# As_Shipped.net
KiCad netlist of a schematic drawn in EAGLE
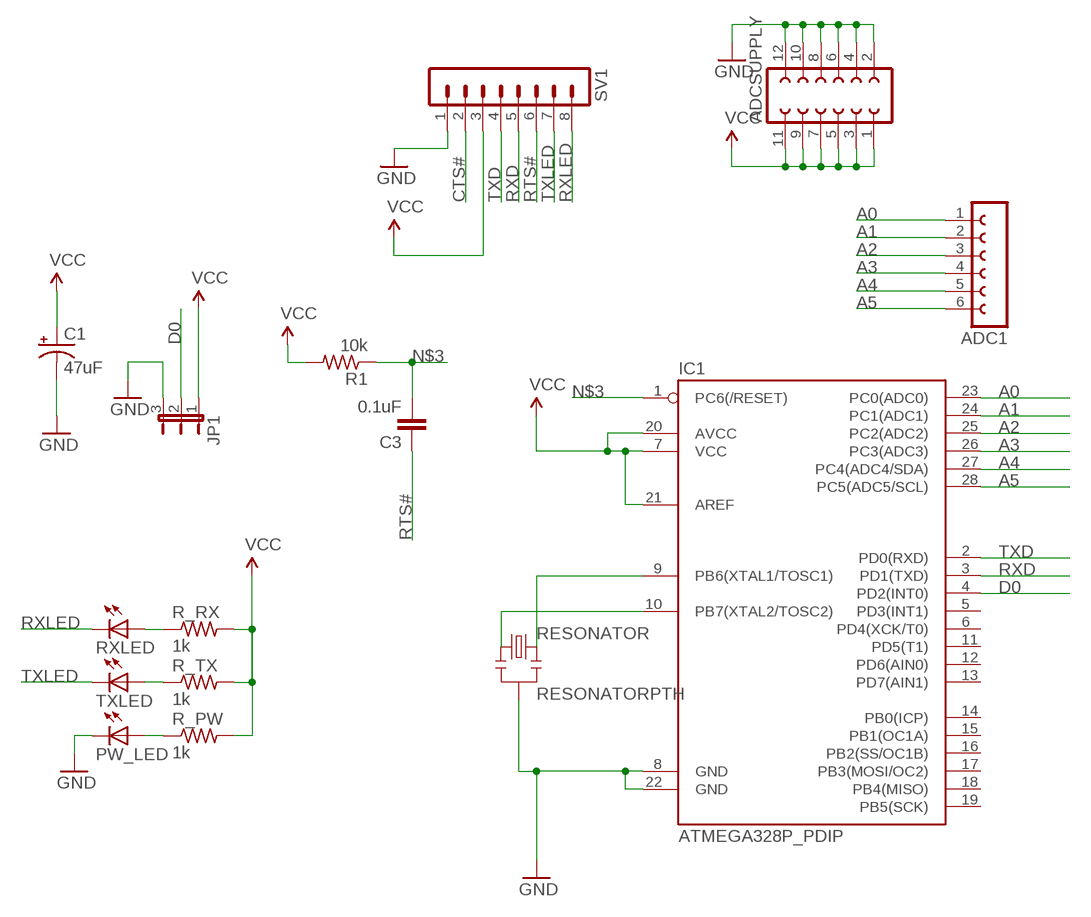
[diagram p0: schematic, sheet 1]

(export (version "E")
  (design (tool "Eeschema 10.0.6"))
  (components
    (comp (ref "ADC1")
      (value "FE06-1")
      (footprint "eagle-import:FE06")
      (libsource (lib "eagle-import") (part "FE06-1"))
    )
    (comp (ref "ADCSUPPLY")
      (value "FE06-2")
      (footprint "eagle-import:FE06-2")
      (libsource (lib "eagle-import") (part "FE06-2"))
    )
    (comp (ref "C1")
      (value "47uF")
      (footprint "eagle-import:E2,5-6E")
      (libsource (lib "eagle-import") (part "CPOL-USE2,5-6E"))
    )
    (comp (ref "C3")
      (value "0.1uF")
      (footprint "eagle-import:0402-CAP")
      (libsource (lib "eagle-import") (part "CAP0402-CAP"))
    )
    (comp (ref "IC1")
      (value "ATMEGA328P_PDIP")
      (footprint "eagle-import:DIL28-3")
      (libsource (lib "eagle-import") (part "ATMEGA328P_PDIP"))
    )
    (comp (ref "JP1")
      (value "JP2E")
      (footprint "eagle-import:JP2")
      (libsource (lib "eagle-import") (part "JP2E"))
    )
    (comp (ref "PW_LED")
      (value "LED5MM")
      (footprint "eagle-import:LED5MM")
      (libsource (lib "eagle-import") (part "LED5MM"))
    )
    (comp (ref "R1")
      (value "10k")
      (footprint "eagle-import:R0805")
      (libsource (lib "eagle-import") (part "R-US_R0805"))
    )
    (comp (ref "RESONATOR")
      (value "RESONATORPTH")
      (footprint "eagle-import:RESONATOR-PTH")
      (libsource (lib "eagle-import") (part "RESONATORPTH"))
    )
    (comp (ref "RXLED")
      (value "LED5MM")
      (footprint "eagle-import:LED5MM")
      (libsource (lib "eagle-import") (part "LED5MM"))
    )
    (comp (ref "R_PW")
      (value "1k")
      (footprint "eagle-import:R0805")
      (libsource (lib "eagle-import") (part "R-US_R0805"))
    )
    (comp (ref "R_RX")
      (value "1k")
      (footprint "eagle-import:R0805")
      (libsource (lib "eagle-import") (part "R-US_R0805"))
    )
    (comp (ref "R_TX")
      (value "1k")
      (footprint "eagle-import:R0805")
      (libsource (lib "eagle-import") (part "R-US_R0805"))
    )
    (comp (ref "SV1")
      (value "MA08-1W")
      (footprint "eagle-import:MA08-1W")
      (libsource (lib "eagle-import") (part "MA08-1W"))
    )
    (comp (ref "TXLED")
      (value "LED5MM")
      (footprint "eagle-import:LED5MM")
      (libsource (lib "eagle-import") (part "LED5MM"))
    )
  )
  (nets
    (net (code "1") (name "/A0") (class "Default")
      (node (ref "ADC1") (pin "1") (pinfunction "1_1") (pintype "passive"))
      (node (ref "IC1") (pin "23") (pinfunction "PC0(ADC0)_23") (pintype "bidirectional"))
    )
    (net (code "2") (name "/A1") (class "Default")
      (node (ref "ADC1") (pin "2") (pinfunction "2_2") (pintype "passive"))
      (node (ref "IC1") (pin "24") (pinfunction "PC1(ADC1)_24") (pintype "bidirectional"))
    )
    (net (code "3") (name "/A2") (class "Default")
      (node (ref "ADC1") (pin "3") (pinfunction "3_3") (pintype "passive"))
      (node (ref "IC1") (pin "25") (pinfunction "PC2(ADC2)_25") (pintype "bidirectional"))
    )
    (net (code "4") (name "/A3") (class "Default")
      (node (ref "ADC1") (pin "4") (pinfunction "4_4") (pintype "passive"))
      (node (ref "IC1") (pin "26") (pinfunction "PC3(ADC3)_26") (pintype "bidirectional"))
    )
    (net (code "5") (name "/A4") (class "Default")
      (node (ref "ADC1") (pin "5") (pinfunction "5_5") (pintype "passive"))
      (node (ref "IC1") (pin "27") (pinfunction "PC4(ADC4/SDA)_27") (pintype "bidirectional"))
    )
    (net (code "6") (name "/A5") (class "Default")
      (node (ref "ADC1") (pin "6") (pinfunction "6_6") (pintype "passive"))
      (node (ref "IC1") (pin "28") (pinfunction "PC5(ADC5/SCL)_28") (pintype "bidirectional"))
    )
    (net (code "7") (name "/CTS#") (class "Default")
      (node (ref "SV1") (pin "2") (pinfunction "2_2") (pintype "passive"))
    )
    (net (code "8") (name "/D0") (class "Default")
      (node (ref "IC1") (pin "4") (pinfunction "PD2(INT0)_4") (pintype "bidirectional"))
      (node (ref "JP1") (pin "2") (pinfunction "2_2") (pintype "passive"))
    )
    (net (code "9") (name "/N$3") (class "Default")
      (node (ref "C3") (pin "2") (pinfunction "2_2") (pintype "passive"))
      (node (ref "IC1") (pin "1") (pinfunction "PC6(/RESET)_1") (pintype "bidirectional"))
      (node (ref "R1") (pin "1") (pinfunction "1_1") (pintype "passive"))
    )
    (net (code "10") (name "/RTS#") (class "Default")
      (node (ref "C3") (pin "1") (pinfunction "1_1") (pintype "passive"))
      (node (ref "SV1") (pin "6") (pinfunction "6_6") (pintype "passive"))
    )
    (net (code "11") (name "/RXD") (class "Default")
      (node (ref "IC1") (pin "3") (pinfunction "PD1(TXD)_3") (pintype "bidirectional"))
      (node (ref "SV1") (pin "5") (pinfunction "5_5") (pintype "passive"))
    )
    (net (code "12") (name "/RXLED") (class "Default")
      (node (ref "RXLED") (pin "K") (pinfunction "C_K") (pintype "passive"))
      (node (ref "SV1") (pin "8") (pinfunction "8_8") (pintype "passive"))
    )
    (net (code "13") (name "/TXD") (class "Default")
      (node (ref "IC1") (pin "2") (pinfunction "PD0(RXD)_2") (pintype "bidirectional"))
      (node (ref "SV1") (pin "4") (pinfunction "4_4") (pintype "passive"))
    )
    (net (code "14") (name "/TXLED") (class "Default")
      (node (ref "SV1") (pin "7") (pinfunction "7_7") (pintype "passive"))
      (node (ref "TXLED") (pin "K") (pinfunction "C_K") (pintype "passive"))
    )
    (net (code "15") (name "GND") (class "Default")
      (node (ref "ADCSUPPLY") (pin "10") (pinfunction "10_10") (pintype "passive"))
      (node (ref "ADCSUPPLY") (pin "12") (pinfunction "12_12") (pintype "passive"))
      (node (ref "ADCSUPPLY") (pin "2") (pinfunction "2_2") (pintype "passive"))
      (node (ref "ADCSUPPLY") (pin "4") (pinfunction "4_4") (pintype "passive"))
      (node (ref "ADCSUPPLY") (pin "6") (pinfunction "6_6") (pintype "passive"))
      (node (ref "ADCSUPPLY") (pin "8") (pinfunction "8_8") (pintype "passive"))
      (node (ref "C1") (pin "-") (pinfunction "-_-") (pintype "passive"))
      (node (ref "IC1") (pin "22") (pinfunction "GND_22") (pintype "bidirectional"))
      (node (ref "IC1") (pin "8") (pinfunction "GND_8") (pintype "bidirectional"))
      (node (ref "JP1") (pin "3") (pinfunction "3_3") (pintype "passive"))
      (node (ref "PW_LED") (pin "K") (pinfunction "C_K") (pintype "passive"))
      (node (ref "RESONATOR") (pin "2") (pinfunction "2_2") (pintype "passive"))
      (node (ref "SV1") (pin "1") (pinfunction "1_1") (pintype "passive"))
    )
    (net (code "16") (name "Net-(IC1-PB6(XTAL1{slash}TOSC1))") (class "Default")
      (node (ref "IC1") (pin "9") (pinfunction "PB6(XTAL1/TOSC1)_9") (pintype "bidirectional"))
      (node (ref "RESONATOR") (pin "3") (pinfunction "3_3") (pintype "passive"))
    )
    (net (code "17") (name "Net-(IC1-PB7(XTAL2{slash}TOSC2))") (class "Default")
      (node (ref "IC1") (pin "10") (pinfunction "PB7(XTAL2/TOSC2)_10") (pintype "bidirectional"))
      (node (ref "RESONATOR") (pin "1") (pinfunction "1_1") (pintype "passive"))
    )
    (net (code "18") (name "Net-(PW_LED-PadA)") (class "Default")
      (node (ref "PW_LED") (pin "A") (pinfunction "A_A") (pintype "passive"))
      (node (ref "R_PW") (pin "1") (pinfunction "1_1") (pintype "passive"))
    )
    (net (code "19") (name "Net-(RXLED-PadA)") (class "Default")
      (node (ref "RXLED") (pin "A") (pinfunction "A_A") (pintype "passive"))
      (node (ref "R_RX") (pin "1") (pinfunction "1_1") (pintype "passive"))
    )
    (net (code "20") (name "Net-(R_TX-Pad1)") (class "Default")
      (node (ref "R_TX") (pin "1") (pinfunction "1_1") (pintype "passive"))
      (node (ref "TXLED") (pin "A") (pinfunction "A_A") (pintype "passive"))
    )
    (net (code "21") (name "VCC") (class "Default")
      (node (ref "ADCSUPPLY") (pin "1") (pinfunction "1_1") (pintype "passive"))
      (node (ref "ADCSUPPLY") (pin "11") (pinfunction "11_11") (pintype "passive"))
      (node (ref "ADCSUPPLY") (pin "3") (pinfunction "3_3") (pintype "passive"))
      (node (ref "ADCSUPPLY") (pin "5") (pinfunction "5_5") (pintype "passive"))
      (node (ref "ADCSUPPLY") (pin "7") (pinfunction "7_7") (pintype "passive"))
      (node (ref "ADCSUPPLY") (pin "9") (pinfunction "9_9") (pintype "passive"))
      (node (ref "C1") (pin "+") (pinfunction "+_+") (pintype "passive"))
      (node (ref "IC1") (pin "20") (pinfunction "AVCC_20") (pintype "bidirectional"))
      (node (ref "IC1") (pin "21") (pinfunction "AREF_21") (pintype "bidirectional"))
      (node (ref "IC1") (pin "7") (pinfunction "VCC_7") (pintype "bidirectional"))
      (node (ref "JP1") (pin "1") (pinfunction "1_1") (pintype "passive"))
      (node (ref "R1") (pin "2") (pinfunction "2_2") (pintype "passive"))
      (node (ref "R_PW") (pin "2") (pinfunction "2_2") (pintype "passive"))
      (node (ref "R_RX") (pin "2") (pinfunction "2_2") (pintype "passive"))
      (node (ref "R_TX") (pin "2") (pinfunction "2_2") (pintype "passive"))
      (node (ref "SV1") (pin "3") (pinfunction "3_3") (pintype "passive"))
    )
    (net (code "22") (name "unconnected-(IC1-PB0(ICP)-Pad14)") (class "Default")
      (node (ref "IC1") (pin "14") (pinfunction "PB0(ICP)_14") (pintype "bidirectional"))
    )
    (net (code "23") (name "unconnected-(IC1-PB1(OC1A)-Pad15)") (class "Default")
      (node (ref "IC1") (pin "15") (pinfunction "PB1(OC1A)_15") (pintype "bidirectional"))
    )
    (net (code "24") (name "unconnected-(IC1-PB2(SS{slash}OC1B)-Pad16)") (class "Default")
      (node (ref "IC1") (pin "16") (pinfunction "PB2(SS/OC1B)_16") (pintype "bidirectional"))
    )
    (net (code "25") (name "unconnected-(IC1-PB3(MOSI{slash}OC2)-Pad17)") (class "Default")
      (node (ref "IC1") (pin "17") (pinfunction "PB3(MOSI/OC2)_17") (pintype "bidirectional"))
    )
    (net (code "26") (name "unconnected-(IC1-PB4(MISO)-Pad18)") (class "Default")
      (node (ref "IC1") (pin "18") (pinfunction "PB4(MISO)_18") (pintype "bidirectional"))
    )
    (net (code "27") (name "unconnected-(IC1-PB5(SCK)-Pad19)") (class "Default")
      (node (ref "IC1") (pin "19") (pinfunction "PB5(SCK)_19") (pintype "bidirectional"))
    )
    (net (code "28") (name "unconnected-(IC1-PD3(INT1)-Pad5)") (class "Default")
      (node (ref "IC1") (pin "5") (pinfunction "PD3(INT1)_5") (pintype "bidirectional"))
    )
    (net (code "29") (name "unconnected-(IC1-PD4(XCK{slash}T0)-Pad6)") (class "Default")
      (node (ref "IC1") (pin "6") (pinfunction "PD4(XCK/T0)_6") (pintype "bidirectional"))
    )
    (net (code "30") (name "unconnected-(IC1-PD5(T1)-Pad11)") (class "Default")
      (node (ref "IC1") (pin "11") (pinfunction "PD5(T1)_11") (pintype "bidirectional"))
    )
    (net (code "31") (name "unconnected-(IC1-PD6(AIN0)-Pad12)") (class "Default")
      (node (ref "IC1") (pin "12") (pinfunction "PD6(AIN0)_12") (pintype "bidirectional"))
    )
    (net (code "32") (name "unconnected-(IC1-PD7(AIN1)-Pad13)") (class "Default")
      (node (ref "IC1") (pin "13") (pinfunction "PD7(AIN1)_13") (pintype "bidirectional"))
    )
  )
)
